# USB_PER2.net
KiCad netlist of a schematic drawn in Altium Designer
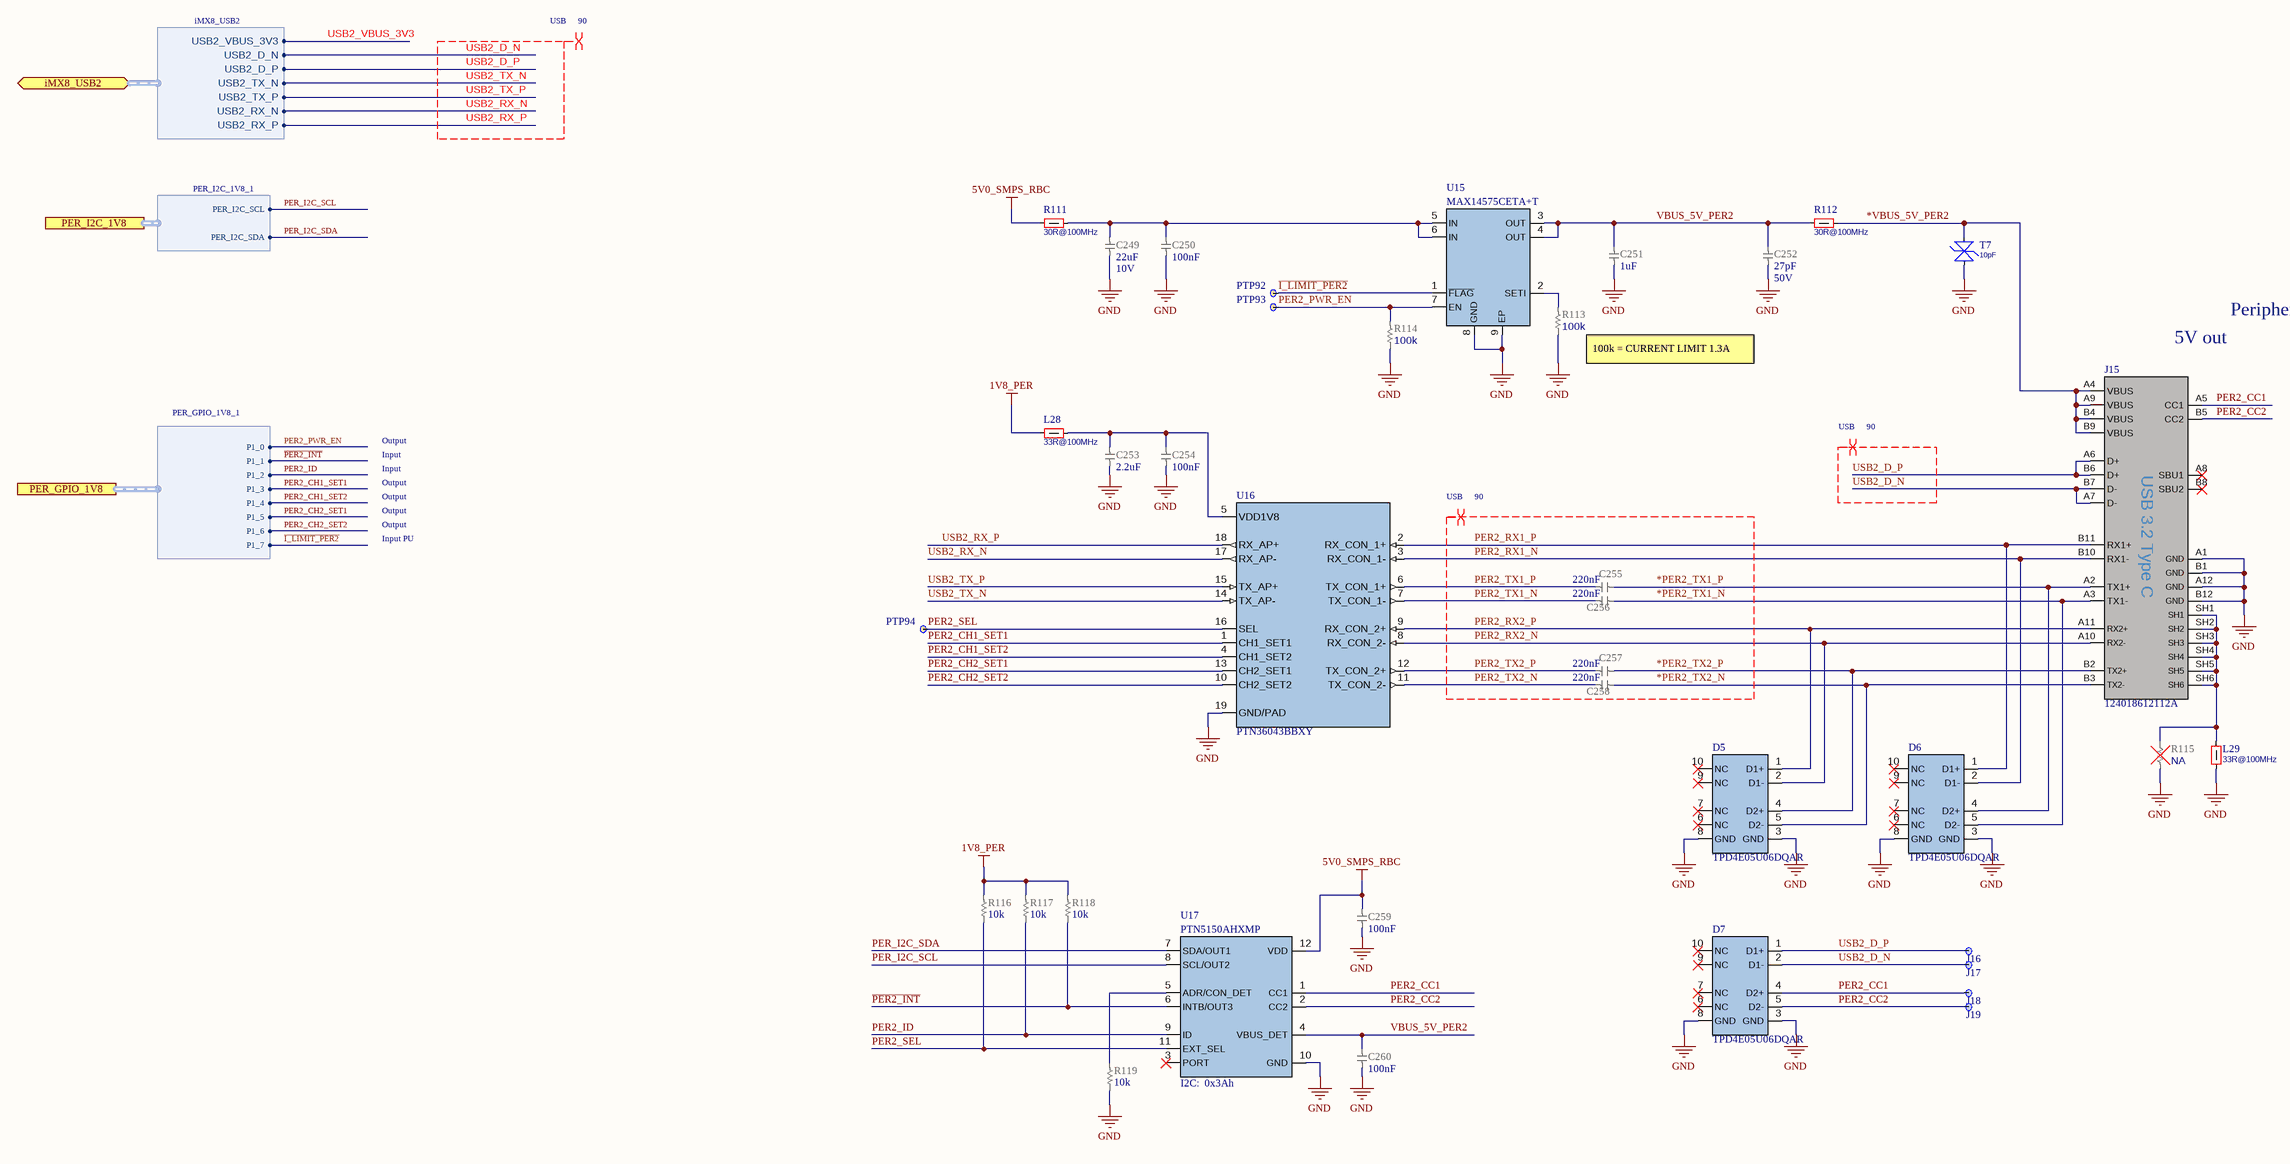
[diagram p0: USB_PER2.SchDoc]

(export (version "E")
  (design (tool "Eeschema 10.0.6"))
  (components
    (comp (ref "C249")
      (value "22uF")
      (footprint "CAP_0805_UN1Q")
      (description "CAP")
      (fields
        (field (name "VOLTAGE") "10V")
        (field (name "TOLERANCE") "+/-20%")
        (field (name "PART NUMBER") "GRM21BZ71A226ME15L")
      )
      (libsource (lib "robo_cam") (part "CMP-001-000892-11"))
    )
    (comp (ref "C250")
      (value "100nF")
      (footprint "CAP_0201_UN1Q")
      (description "CAP")
      (fields (field (name "PART NUMBER") "GRM033C71C104KE14D") (field (name "MANUFACTURER") "Murata"))
      (libsource (lib "robo_cam") (part "CMP-001-000385-16"))
    )
    (comp (ref "C251")
      (value "1uF")
      (footprint "CAP_0201_UN1Q")
      (description "CAP")
      (fields (field (name "PART NUMBER") "KGM03CS61A105MH") (field (name "MANUFACTURER") "Kyocera"))
      (libsource (lib "robo_cam") (part "CMP-001-000336-15"))
    )
    (comp (ref "C252")
      (value "27pF")
      (footprint "CAP_0201_UN1Q")
      (description "CAP")
      (fields
        (field (name "PART NUMBER") "GRM0335C1H270JA01D")
        (field (name "MANUFACTURER") "TDK")
        (field (name "VOLTAGE") "50V")
      )
      (libsource (lib "robo_cam") (part "CMP-001-000280-15"))
    )
    (comp (ref "C253")
      (value "2.2uF")
      (footprint "CAP_0402_H09W07_UN1Q")
      (description "CAP")
      (fields (field (name "PART NUMBER") "GRM155C81A225KE44D") (field (name "MANUFACTURER") "Murata"))
      (libsource (lib "robo_cam") (part "CMP-001-000887-10"))
    )
    (comp (ref "C254")
      (value "100nF")
      (footprint "CAP_0201_UN1Q")
      (description "CAP")
      (fields (field (name "PART NUMBER") "GRM033C71C104KE14D") (field (name "MANUFACTURER") "Murata"))
      (libsource (lib "robo_cam") (part "CMP-001-000385-16"))
    )
    (comp (ref "C255")
      (value "220nF")
      (footprint "CAP_0201_UN1Q")
      (description "CAP")
      (fields (field (name "PART NUMBER") "GRM033C81A224KE01D") (field (name "MANUFACTURER") "Murata"))
      (libsource (lib "robo_cam") (part "CMP-001-000889-11"))
    )
    (comp (ref "C256")
      (value "220nF")
      (footprint "CAP_0201_UN1Q")
      (description "CAP")
      (fields (field (name "PART NUMBER") "GRM033C81A224KE01D") (field (name "MANUFACTURER") "Murata"))
      (libsource (lib "robo_cam") (part "CMP-001-000889-11"))
    )
    (comp (ref "C257")
      (value "220nF")
      (footprint "CAP_0201_UN1Q")
      (description "CAP")
      (fields (field (name "PART NUMBER") "GRM033C81A224KE01D") (field (name "MANUFACTURER") "Murata"))
      (libsource (lib "robo_cam") (part "CMP-001-000889-11"))
    )
    (comp (ref "C258")
      (value "220nF")
      (footprint "CAP_0201_UN1Q")
      (description "CAP")
      (fields (field (name "PART NUMBER") "GRM033C81A224KE01D") (field (name "MANUFACTURER") "Murata"))
      (libsource (lib "robo_cam") (part "CMP-001-000889-11"))
    )
    (comp (ref "C259")
      (value "100nF")
      (footprint "CAP_0201_UN1Q")
      (description "CAP")
      (fields (field (name "PART NUMBER") "GRM033C71C104KE14D") (field (name "MANUFACTURER") "Murata"))
      (libsource (lib "robo_cam") (part "CMP-001-000385-16"))
    )
    (comp (ref "C260")
      (value "100nF")
      (footprint "CAP_0201_UN1Q")
      (description "CAP")
      (fields (field (name "PART NUMBER") "GRM033C71C104KE14D") (field (name "MANUFACTURER") "Murata"))
      (libsource (lib "robo_cam") (part "CMP-001-000385-16"))
    )
    (comp (ref "D5")
      (value "TPD4E05U06DQAR")
      (footprint "USON10_DQA_TI")
      (description "4-CH Low-Capacitance ESD Diode")
      (fields
        (field (name "MANUFACTURER") "Texas Instruments")
        (field (name "SOURCE") "UUDET_KOMPONENTIT.SchLib")
      )
      (libsource (lib "robo_cam") (part "CMP-001-000916-4"))
    )
    (comp (ref "D6")
      (value "TPD4E05U06DQAR")
      (footprint "USON10_DQA_TI")
      (description "4-CH Low-Capacitance ESD Diode")
      (fields
        (field (name "MANUFACTURER") "Texas Instruments")
        (field (name "SOURCE") "UUDET_KOMPONENTIT.SchLib")
      )
      (libsource (lib "robo_cam") (part "CMP-001-000916-4"))
    )
    (comp (ref "D7")
      (value "TPD4E05U06DQAR")
      (footprint "USON10_DQA_TI")
      (description "4-CH Low-Capacitance ESD Diode")
      (fields
        (field (name "MANUFACTURER") "Texas Instruments")
        (field (name "SOURCE") "UUDET_KOMPONENTIT.SchLib")
      )
      (libsource (lib "robo_cam") (part "CMP-001-000916-4"))
    )
    (comp (ref "J15")
      (value "USB_C_AMPHENOL_124018612112A")
      (footprint "USB_C_AMPHENOL_124018612112A")
      (description "USB3.2 GEN1, Type C, Top mount, CH 1.50mm, Dual Row SMT, IPX8")
      (fields
        (field (name "PART NUMBER") "124018612112A")
        (field (name "MANUFACTURER") "Amphenol")
        (field (name "MANUFACTURER PART NUMBER") "12402082E512A")
      )
      (libsource (lib "robo_cam") (part "CMP-001-001438-8"))
    )
    (comp (ref "J16")
      (value "Testpoint, Surface, 1.0mm")
      (footprint "TP_1mm_UN1Q")
      (description "Testpoint 1.0mm")
      (fields (field (name "PART NUMBER") "TP 1mm"))
      (libsource (lib "robo_cam") (part "CMP-001-000153-12"))
    )
    (comp (ref "J17")
      (value "Testpoint, Surface, 1.0mm")
      (footprint "TP_1mm_UN1Q")
      (description "Testpoint 1.0mm")
      (fields (field (name "PART NUMBER") "TP 1mm"))
      (libsource (lib "robo_cam") (part "CMP-001-000153-12"))
    )
    (comp (ref "J18")
      (value "Testpoint, Surface, 1.0mm")
      (footprint "TP_1mm_UN1Q")
      (description "Testpoint 1.0mm")
      (fields (field (name "PART NUMBER") "TP 1mm"))
      (libsource (lib "robo_cam") (part "CMP-001-000153-12"))
    )
    (comp (ref "J19")
      (value "Testpoint, Surface, 1.0mm")
      (footprint "TP_1mm_UN1Q")
      (description "Testpoint 1.0mm")
      (fields (field (name "PART NUMBER") "TP 1mm"))
      (libsource (lib "robo_cam") (part "CMP-001-000153-12"))
    )
    (comp (ref "L28")
      (value "33R@100MHz")
      (footprint "IND_0201_UN1Q")
      (description "FERRITE")
      (fields (field (name "MANUFACTURER") "Murata") (field (name "TOLERANCE") "25%"))
      (libsource (lib "robo_cam") (part "CMP-001-000744-7"))
    )
    (comp (ref "L29")
      (value "33R@100MHz")
      (footprint "IND_0201_UN1Q")
      (description "FERRITE")
      (fields (field (name "MANUFACTURER") "Murata") (field (name "TOLERANCE") "25%"))
      (libsource (lib "robo_cam") (part "CMP-001-000744-7"))
    )
    (comp (ref "PTP92")
      (value "PTP_0.4mm")
      (footprint "PTP_0.4mm")
      (description "Production Testpoint 0.4mm. Flying probe. Use 1mm pitch.")
      (fields (field (name "PART NUMBER") "PTP 0.4mm"))
      (libsource (lib "robo_cam") (part "CMP-001-001296-3"))
    )
    (comp (ref "PTP93")
      (value "PTP_0.4mm")
      (footprint "PTP_0.4mm")
      (description "Production Testpoint 0.4mm. Flying probe. Use 1mm pitch.")
      (fields (field (name "PART NUMBER") "PTP 0.4mm"))
      (libsource (lib "robo_cam") (part "CMP-001-001296-3"))
    )
    (comp (ref "PTP94")
      (value "PTP_0.4mm")
      (footprint "PTP_0.4mm")
      (description "Production Testpoint 0.4mm. Flying probe. Use 1mm pitch.")
      (fields (field (name "PART NUMBER") "PTP 0.4mm"))
      (libsource (lib "robo_cam") (part "CMP-001-001296-3"))
    )
    (comp (ref "R111")
      (value "30R@100MHz")
      (footprint "FERR_BLM15KD")
      (description "FERRITE")
      (fields (field (name "PART NUMBER") "BLM15KD300SN1") (field (name "MANUFACTURER") "Murata"))
      (libsource (lib "robo_cam") (part "CMP-001-000738-12"))
    )
    (comp (ref "R112")
      (value "30R@100MHz")
      (footprint "FERR_BLM15KD")
      (description "FERRITE")
      (fields (field (name "PART NUMBER") "BLM15KD300SN1") (field (name "MANUFACTURER") "Murata"))
      (libsource (lib "robo_cam") (part "CMP-001-000738-12"))
    )
    (comp (ref "R113")
      (value "100k")
      (footprint "RES_0201_UN1Q")
      (description "RES")
      (fields (field (name "TOLERANCE") "1%") (field (name "PART NUMBER") "RC0201FR-07100KL"))
      (libsource (lib "robo_cam") (part "CMP-001-000526-11"))
    )
    (comp (ref "R114")
      (value "100k")
      (footprint "RES_0201_UN1Q")
      (description "RES")
      (fields (field (name "TOLERANCE") "1%") (field (name "PART NUMBER") "RC0201FR-07100KL"))
      (libsource (lib "robo_cam") (part "CMP-001-000526-11"))
    )
    (comp (ref "R115")
      (value "NA")
      (footprint "RES_0201_UN1Q")
      (description "Not Assembled - RES")
      (fields (field (name "Comment") "RES_0201_NA"))
      (libsource (lib "robo_cam") (part "CMP-001-000434-10"))
    )
    (comp (ref "R116")
      (value "10k")
      (footprint "RES_0201_UN1Q")
      (description "RES")
      (fields (field (name "PART NUMBER") "RC0201FR-0710KL") (field (name "MANUFACTURER") "YAGEO"))
      (libsource (lib "robo_cam") (part "CMP-001-000446-13"))
    )
    (comp (ref "R117")
      (value "10k")
      (footprint "RES_0201_UN1Q")
      (description "RES")
      (fields (field (name "PART NUMBER") "RC0201FR-0710KL") (field (name "MANUFACTURER") "YAGEO"))
      (libsource (lib "robo_cam") (part "CMP-001-000446-13"))
    )
    (comp (ref "R118")
      (value "10k")
      (footprint "RES_0201_UN1Q")
      (description "RES")
      (fields (field (name "PART NUMBER") "RC0201FR-0710KL") (field (name "MANUFACTURER") "YAGEO"))
      (libsource (lib "robo_cam") (part "CMP-001-000446-13"))
    )
    (comp (ref "R119")
      (value "10k")
      (footprint "RES_0201_UN1Q")
      (description "RES")
      (fields (field (name "PART NUMBER") "RC0201FR-0710KL") (field (name "MANUFACTURER") "YAGEO"))
      (libsource (lib "robo_cam") (part "CMP-001-000446-13"))
    )
    (comp (ref "T7")
      (value "10pF")
      (footprint "TVS_0201_EZAEG")
      (description "ESD Protection  TVS Diodes SMP Diode 0201 5vdc 10 pf <8v clamp@1a")
      (fields (field (name "PART NUMBER") "GG020105100N2P") (field (name "MANUFACTURER") "TDK"))
      (libsource (lib "robo_cam") (part "CMP-001-000756-6"))
    )
    (comp (ref "U15")
      (value "MAX14575C")
      (footprint "TDFN8-MAX14575C")
      (description "ADJ. CURRENT-LIMITED POWER SWITCH, 2.5A")
      (fields (field (name "PART NUMBER") "MAX14575CETA+T") (field (name "MANUFACTURER") "Maxim Integrated"))
      (libsource (lib "TII_WS") (part "MAX14575C"))
    )
    (comp (ref "U16")
      (value "PTN36043BBXY")
      (footprint "DHX2QFN18_NXP")
      (description "USB3.1 Gen1 Type-C Superspeed Active Signal Switch")
      (fields
        (field (name "MANUFACTURER") "NXP")
        (field (name "PART NUMBER") "PTN36043BBXY")
        (field (name "MANUFACTURER_1") "Knowles")
      )
      (libsource (lib "robo_cam") (part "CMP-001-001164-4"))
    )
    (comp (ref "U17")
      (value "PTN5150AHXMP")
      (footprint "X2QFN12_NXP")
      (description "CC logic for USB Type-C applications")
      (fields (field (name "MANUFACTURER") "NXP") (field (name "PART NUMBER") "PTN5150AHXMP"))
      (libsource (lib "TII_WS") (part "PTN5150AHXMP"))
    )
  )
  (nets
    (net (code "4") (name "/*PER2_TX1_N") (class "Default")
      (node (ref "C256") (pin "1") (pinfunction "1_1") (pintype "passive"))
      (node (ref "D6") (pin "5") (pinfunction "D2-_5") (pintype "passive"))
      (node (ref "J15") (pin "A3") (pinfunction "TX1-_A3") (pintype "passive"))
    )
    (net (code "5") (name "/*PER2_TX1_P") (class "Default")
      (node (ref "C255") (pin "1") (pinfunction "1_1") (pintype "passive"))
      (node (ref "D6") (pin "4") (pinfunction "D2+_4") (pintype "passive"))
      (node (ref "J15") (pin "A2") (pinfunction "TX1+_A2") (pintype "passive"))
    )
    (net (code "6") (name "/*PER2_TX2_N") (class "Default")
      (node (ref "C258") (pin "1") (pinfunction "1_1") (pintype "passive"))
      (node (ref "D5") (pin "5") (pinfunction "D2-_5") (pintype "passive"))
      (node (ref "J15") (pin "B3") (pinfunction "TX2-_B3") (pintype "passive"))
    )
    (net (code "7") (name "/*PER2_TX2_P") (class "Default")
      (node (ref "C257") (pin "1") (pinfunction "1_1") (pintype "passive"))
      (node (ref "D5") (pin "4") (pinfunction "D2+_4") (pintype "passive"))
      (node (ref "J15") (pin "B2") (pinfunction "TX2+_B2") (pintype "passive"))
    )
    (net (code "8") (name "/*VBUS_5V_PER2") (class "Default")
      (node (ref "J15") (pin "A4") (pinfunction "VBUS_A4") (pintype "passive"))
      (node (ref "J15") (pin "A9") (pinfunction "VBUS_A9") (pintype "passive"))
      (node (ref "J15") (pin "B4") (pinfunction "VBUS_B4") (pintype "passive"))
      (node (ref "J15") (pin "B9") (pinfunction "VBUS_B9") (pintype "passive"))
      (node (ref "R112") (pin "2") (pinfunction "2_2") (pintype "passive"))
      (node (ref "T7") (pin "2") (pinfunction "2_2") (pintype "passive"))
    )
    (net (code "9") (name "/I_LIMIT_PER2") (class "Default")
      (node (ref "PTP92") (pin "1") (pinfunction "TP_1") (pintype "passive"))
      (node (ref "U15") (pin "1") (pinfunction "~{FLAG}_1") (pintype "passive"))
    )
    (net (code "10") (name "/PER2_CC1") (class "Default")
      (node (ref "D7") (pin "4") (pinfunction "D2+_4") (pintype "passive"))
      (node (ref "J15") (pin "A5") (pinfunction "CC1_A5") (pintype "passive"))
      (node (ref "J18") (pin "1") (pinfunction "TP_1") (pintype "passive"))
      (node (ref "U17") (pin "1") (pinfunction "CC1_1") (pintype "passive"))
    )
    (net (code "11") (name "/PER2_CC2") (class "Default")
      (node (ref "D7") (pin "5") (pinfunction "D2-_5") (pintype "passive"))
      (node (ref "J15") (pin "B5") (pinfunction "CC2_B5") (pintype "passive"))
      (node (ref "J19") (pin "1") (pinfunction "TP_1") (pintype "passive"))
      (node (ref "U17") (pin "2") (pinfunction "CC2_2") (pintype "passive"))
    )
    (net (code "12") (name "/PER2_CH1_SET1") (class "Default")
      (node (ref "U16") (pin "1") (pinfunction "CH1_SET1_1") (pintype "passive"))
    )
    (net (code "13") (name "/PER2_CH1_SET2") (class "Default")
      (node (ref "U16") (pin "4") (pinfunction "CH1_SET2_4") (pintype "passive"))
    )
    (net (code "14") (name "/PER2_CH2_SET1") (class "Default")
      (node (ref "U16") (pin "13") (pinfunction "CH2_SET1_13") (pintype "passive"))
    )
    (net (code "15") (name "/PER2_CH2_SET2") (class "Default")
      (node (ref "U16") (pin "10") (pinfunction "CH2_SET2_10") (pintype "passive"))
    )
    (net (code "16") (name "/PER2_ID") (class "Default")
      (node (ref "R117") (pin "1") (pinfunction "1_1") (pintype "passive"))
      (node (ref "U17") (pin "9") (pinfunction "ID_9") (pintype "passive"))
    )
    (net (code "17") (name "/PER2_INT") (class "Default")
      (node (ref "R118") (pin "1") (pinfunction "1_1") (pintype "passive"))
      (node (ref "U17") (pin "6") (pinfunction "INTB/OUT3_6") (pintype "passive"))
    )
    (net (code "18") (name "/PER2_PWR_EN") (class "Default")
      (node (ref "PTP93") (pin "1") (pinfunction "TP_1") (pintype "passive"))
      (node (ref "R114") (pin "2") (pinfunction "2_2") (pintype "passive"))
      (node (ref "U15") (pin "7") (pinfunction "EN_7") (pintype "passive"))
    )
    (net (code "19") (name "/PER2_RX1_N") (class "Default")
      (node (ref "D6") (pin "2") (pinfunction "D1-_2") (pintype "passive"))
      (node (ref "J15") (pin "B10") (pinfunction "RX1-_B10") (pintype "passive"))
      (node (ref "U16") (pin "3") (pinfunction "RX_CON_1-_3") (pintype "input"))
    )
    (net (code "20") (name "/PER2_RX1_P") (class "Default")
      (node (ref "D6") (pin "1") (pinfunction "D1+_1") (pintype "passive"))
      (node (ref "J15") (pin "B11") (pinfunction "RX1+_B11") (pintype "passive"))
      (node (ref "U16") (pin "2") (pinfunction "RX_CON_1+_2") (pintype "input"))
    )
    (net (code "21") (name "/PER2_RX2_N") (class "Default")
      (node (ref "D5") (pin "2") (pinfunction "D1-_2") (pintype "passive"))
      (node (ref "J15") (pin "A10") (pinfunction "RX2-_A10") (pintype "passive"))
      (node (ref "U16") (pin "8") (pinfunction "RX_CON_2-_8") (pintype "input"))
    )
    (net (code "22") (name "/PER2_RX2_P") (class "Default")
      (node (ref "D5") (pin "1") (pinfunction "D1+_1") (pintype "passive"))
      (node (ref "J15") (pin "A11") (pinfunction "RX2+_A11") (pintype "passive"))
      (node (ref "U16") (pin "9") (pinfunction "RX_CON_2+_9") (pintype "input"))
    )
    (net (code "23") (name "/PER2_SEL") (class "Default")
      (node (ref "PTP94") (pin "1") (pinfunction "TP_1") (pintype "passive"))
      (node (ref "R116") (pin "1") (pinfunction "1_1") (pintype "passive"))
      (node (ref "U16") (pin "16") (pinfunction "SEL_16") (pintype "passive"))
      (node (ref "U17") (pin "11") (pinfunction "EXT_SEL_11") (pintype "passive"))
    )
    (net (code "24") (name "/PER2_TX1_N") (class "Default")
      (node (ref "C256") (pin "2") (pinfunction "2_2") (pintype "passive"))
      (node (ref "U16") (pin "7") (pinfunction "TX_CON_1-_7") (pintype "output"))
    )
    (net (code "25") (name "/PER2_TX1_P") (class "Default")
      (node (ref "C255") (pin "2") (pinfunction "2_2") (pintype "passive"))
      (node (ref "U16") (pin "6") (pinfunction "TX_CON_1+_6") (pintype "output"))
    )
    (net (code "26") (name "/PER2_TX2_N") (class "Default")
      (node (ref "C258") (pin "2") (pinfunction "2_2") (pintype "passive"))
      (node (ref "U16") (pin "11") (pinfunction "TX_CON_2-_11") (pintype "output"))
    )
    (net (code "27") (name "/PER2_TX2_P") (class "Default")
      (node (ref "C257") (pin "2") (pinfunction "2_2") (pintype "passive"))
      (node (ref "U16") (pin "12") (pinfunction "TX_CON_2+_12") (pintype "output"))
    )
    (net (code "28") (name "/PER_I2C_SCL") (class "Default")
      (node (ref "U17") (pin "8") (pinfunction "SCL/OUT2_8") (pintype "passive"))
    )
    (net (code "29") (name "/PER_I2C_SDA") (class "Default")
      (node (ref "U17") (pin "7") (pinfunction "SDA/OUT1_7") (pintype "passive"))
    )
    (net (code "30") (name "/USB2_D_N") (class "Default")
      (node (ref "D7") (pin "2") (pinfunction "D1-_2") (pintype "passive"))
      (node (ref "J15") (pin "A7") (pinfunction "D-_A7") (pintype "passive"))
      (node (ref "J15") (pin "B7") (pinfunction "D-_B7") (pintype "passive"))
      (node (ref "J17") (pin "1") (pinfunction "TP_1") (pintype "passive"))
    )
    (net (code "31") (name "/USB2_D_P") (class "Default")
      (node (ref "D7") (pin "1") (pinfunction "D1+_1") (pintype "passive"))
      (node (ref "J15") (pin "A6") (pinfunction "D+_A6") (pintype "passive"))
      (node (ref "J15") (pin "B6") (pinfunction "D+_B6") (pintype "passive"))
      (node (ref "J16") (pin "1") (pinfunction "TP_1") (pintype "passive"))
    )
    (net (code "32") (name "/USB2_RX_N") (class "Default")
      (node (ref "U16") (pin "17") (pinfunction "RX_AP-_17") (pintype "output"))
    )
    (net (code "33") (name "/USB2_RX_P") (class "Default")
      (node (ref "U16") (pin "18") (pinfunction "RX_AP+_18") (pintype "output"))
    )
    (net (code "34") (name "/USB2_TX_N") (class "Default")
      (node (ref "U16") (pin "14") (pinfunction "TX_AP-_14") (pintype "input"))
    )
    (net (code "35") (name "/USB2_TX_P") (class "Default")
      (node (ref "U16") (pin "15") (pinfunction "TX_AP+_15") (pintype "input"))
    )
    (net (code "37") (name "/VBUS_5V_PER2") (class "Default")
      (node (ref "C251") (pin "2") (pinfunction "2_2") (pintype "passive"))
      (node (ref "C252") (pin "2") (pinfunction "2_2") (pintype "passive"))
      (node (ref "C260") (pin "1") (pinfunction "1_1") (pintype "passive"))
      (node (ref "R112") (pin "1") (pinfunction "1_1") (pintype "passive"))
      (node (ref "U15") (pin "3") (pinfunction "OUT_3") (pintype "passive"))
      (node (ref "U15") (pin "4") (pinfunction "OUT_4") (pintype "passive"))
      (node (ref "U17") (pin "4") (pinfunction "VBUS_DET_4") (pintype "passive"))
    )
    (net (code "41") (name "1V8_PER") (class "Default")
      (node (ref "L28") (pin "1") (pinfunction "1_1") (pintype "passive"))
      (node (ref "R116") (pin "2") (pinfunction "2_2") (pintype "passive"))
      (node (ref "R117") (pin "2") (pinfunction "2_2") (pintype "passive"))
      (node (ref "R118") (pin "2") (pinfunction "2_2") (pintype "passive"))
    )
    (net (code "42") (name "5V0_SMPS_RBC") (class "Default")
      (node (ref "C259") (pin "1") (pinfunction "1_1") (pintype "passive"))
      (node (ref "R111") (pin "1") (pinfunction "1_1") (pintype "passive"))
      (node (ref "U17") (pin "12") (pinfunction "VDD_12") (pintype "passive"))
    )
    (net (code "43") (name "GND") (class "Default")
      (node (ref "C249") (pin "1") (pinfunction "1_1") (pintype "passive"))
      (node (ref "C250") (pin "1") (pinfunction "1_1") (pintype "passive"))
      (node (ref "C251") (pin "1") (pinfunction "1_1") (pintype "passive"))
      (node (ref "C252") (pin "1") (pinfunction "1_1") (pintype "passive"))
      (node (ref "C253") (pin "2") (pinfunction "2_2") (pintype "passive"))
      (node (ref "C254") (pin "2") (pinfunction "2_2") (pintype "passive"))
      (node (ref "C259") (pin "2") (pinfunction "2_2") (pintype "passive"))
      (node (ref "C260") (pin "2") (pinfunction "2_2") (pintype "passive"))
      (node (ref "D5") (pin "3") (pinfunction "GND_3") (pintype "passive"))
      (node (ref "D5") (pin "8") (pinfunction "GND_8") (pintype "passive"))
      (node (ref "D6") (pin "3") (pinfunction "GND_3") (pintype "passive"))
      (node (ref "D6") (pin "8") (pinfunction "GND_8") (pintype "passive"))
      (node (ref "D7") (pin "3") (pinfunction "GND_3") (pintype "passive"))
      (node (ref "D7") (pin "8") (pinfunction "GND_8") (pintype "passive"))
      (node (ref "J15") (pin "A1") (pinfunction "GND_A1") (pintype "passive"))
      (node (ref "J15") (pin "A12") (pinfunction "GND_A12") (pintype "passive"))
      (node (ref "J15") (pin "B1") (pinfunction "GND_B1") (pintype "passive"))
      (node (ref "J15") (pin "B12") (pinfunction "GND_B12") (pintype "passive"))
      (node (ref "L29") (pin "2") (pinfunction "2_2") (pintype "passive"))
      (node (ref "R113") (pin "1") (pinfunction "1_1") (pintype "passive"))
      (node (ref "R114") (pin "1") (pinfunction "1_1") (pintype "passive"))
      (node (ref "R115") (pin "2") (pinfunction "2_2") (pintype "passive"))
      (node (ref "R119") (pin "1") (pinfunction "1_1") (pintype "passive"))
      (node (ref "T7") (pin "1") (pinfunction "1_1") (pintype "passive"))
      (node (ref "U15") (pin "8") (pinfunction "GND_8") (pintype "passive"))
      (node (ref "U15") (pin "9") (pinfunction "EP_9") (pintype "passive"))
      (node (ref "U16") (pin "19") (pinfunction "GND/PAD_19") (pintype "passive"))
      (node (ref "U17") (pin "10") (pinfunction "GND_10") (pintype "passive"))
    )
    (net (code "44") (name "Net-(C249-Pad2)") (class "Default")
      (node (ref "C249") (pin "2") (pinfunction "2_2") (pintype "passive"))
      (node (ref "C250") (pin "2") (pinfunction "2_2") (pintype "passive"))
      (node (ref "R111") (pin "2") (pinfunction "2_2") (pintype "passive"))
      (node (ref "U15") (pin "5") (pinfunction "IN_5") (pintype "passive"))
      (node (ref "U15") (pin "6") (pinfunction "IN_6") (pintype "passive"))
    )
    (net (code "45") (name "Net-(J15-PadSH1)") (class "Default")
      (node (ref "J15") (pin "SH1") (pinfunction "SH1_SH1") (pintype "passive"))
      (node (ref "J15") (pin "SH2") (pinfunction "SH2_SH2") (pintype "passive"))
      (node (ref "J15") (pin "SH3") (pinfunction "SH3_SH3") (pintype "passive"))
      (node (ref "J15") (pin "SH4") (pinfunction "SH4_SH4") (pintype "passive"))
      (node (ref "J15") (pin "SH5") (pinfunction "SH5_SH5") (pintype "passive"))
      (node (ref "J15") (pin "SH6") (pinfunction "SH6_SH6") (pintype "passive"))
      (node (ref "L29") (pin "1") (pinfunction "1_1") (pintype "passive"))
      (node (ref "R115") (pin "1") (pinfunction "1_1") (pintype "passive"))
    )
    (net (code "46") (name "Net-(U15-SETI)") (class "Default")
      (node (ref "R113") (pin "2") (pinfunction "2_2") (pintype "passive"))
      (node (ref "U15") (pin "2") (pinfunction "SETI_2") (pintype "passive"))
    )
    (net (code "47") (name "Net-(U16-VDD1V8)") (class "Default")
      (node (ref "C253") (pin "1") (pinfunction "1_1") (pintype "passive"))
      (node (ref "C254") (pin "1") (pinfunction "1_1") (pintype "passive"))
      (node (ref "L28") (pin "2") (pinfunction "2_2") (pintype "passive"))
      (node (ref "U16") (pin "5") (pinfunction "VDD1V8_5") (pintype "passive"))
    )
    (net (code "48") (name "Net-(U17-ADR{slash}CON_DET)") (class "Default")
      (node (ref "R119") (pin "2") (pinfunction "2_2") (pintype "passive"))
      (node (ref "U17") (pin "5") (pinfunction "ADR/CON_DET_5") (pintype "passive"))
    )
    (net (code "49") (name "unconnected-(D5-NC-Pad6)") (class "Default")
      (node (ref "D5") (pin "6") (pinfunction "NC_6") (pintype "passive+no_connect"))
    )
    (net (code "50") (name "unconnected-(D5-NC-Pad7)") (class "Default")
      (node (ref "D5") (pin "7") (pinfunction "NC_7") (pintype "passive+no_connect"))
    )
    (net (code "51") (name "unconnected-(D5-NC-Pad9)") (class "Default")
      (node (ref "D5") (pin "9") (pinfunction "NC_9") (pintype "passive+no_connect"))
    )
    (net (code "52") (name "unconnected-(D5-NC-Pad10)") (class "Default")
      (node (ref "D5") (pin "10") (pinfunction "NC_10") (pintype "passive+no_connect"))
    )
    (net (code "53") (name "unconnected-(D6-NC-Pad6)") (class "Default")
      (node (ref "D6") (pin "6") (pinfunction "NC_6") (pintype "passive+no_connect"))
    )
    (net (code "54") (name "unconnected-(D6-NC-Pad7)") (class "Default")
      (node (ref "D6") (pin "7") (pinfunction "NC_7") (pintype "passive+no_connect"))
    )
    (net (code "55") (name "unconnected-(D6-NC-Pad9)") (class "Default")
      (node (ref "D6") (pin "9") (pinfunction "NC_9") (pintype "passive+no_connect"))
    )
    (net (code "56") (name "unconnected-(D6-NC-Pad10)") (class "Default")
      (node (ref "D6") (pin "10") (pinfunction "NC_10") (pintype "passive+no_connect"))
    )
    (net (code "57") (name "unconnected-(D7-NC-Pad6)") (class "Default")
      (node (ref "D7") (pin "6") (pinfunction "NC_6") (pintype "passive+no_connect"))
    )
    (net (code "58") (name "unconnected-(D7-NC-Pad7)") (class "Default")
      (node (ref "D7") (pin "7") (pinfunction "NC_7") (pintype "passive+no_connect"))
    )
    (net (code "59") (name "unconnected-(D7-NC-Pad9)") (class "Default")
      (node (ref "D7") (pin "9") (pinfunction "NC_9") (pintype "passive+no_connect"))
    )
    (net (code "60") (name "unconnected-(D7-NC-Pad10)") (class "Default")
      (node (ref "D7") (pin "10") (pinfunction "NC_10") (pintype "passive+no_connect"))
    )
    (net (code "61") (name "unconnected-(J15-SBU1-PadA8)") (class "Default")
      (node (ref "J15") (pin "A8") (pinfunction "SBU1_A8") (pintype "passive+no_connect"))
    )
    (net (code "62") (name "unconnected-(J15-SBU2-PadB8)") (class "Default")
      (node (ref "J15") (pin "B8") (pinfunction "SBU2_B8") (pintype "passive+no_connect"))
    )
    (net (code "63") (name "unconnected-(U17-PORT-Pad3)") (class "Default")
      (node (ref "U17") (pin "3") (pinfunction "PORT_3") (pintype "passive+no_connect"))
    )
  )
)
